# Sheet1.net
KiCad netlist of a schematic drawn in Altium Designer
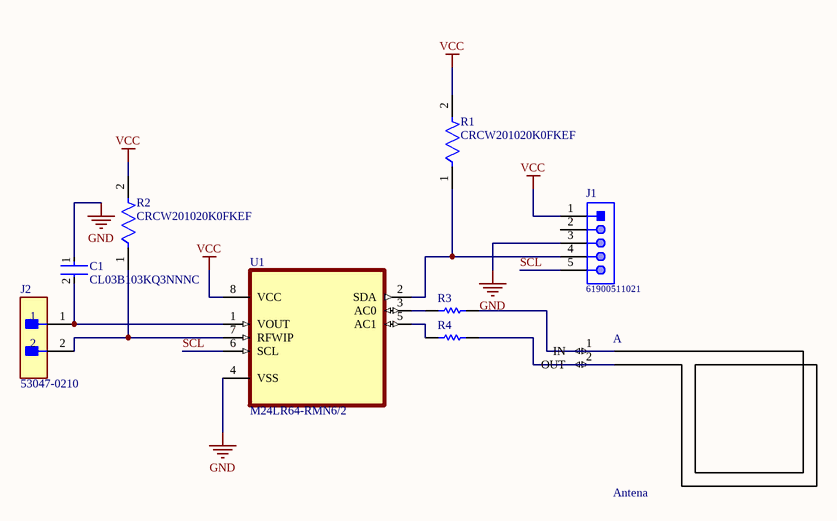
[diagram p0: Sheet1.SchDoc]

(export (version "E")
  (design (tool "Eeschema 10.0.6"))
  (components
    (comp (ref "A") (value "Antena") (footprint "Antena2") (libsource (lib "ANtene_symbol") (part "Antena")))
    (comp (ref "C1")
      (value "CL03B103KQ3NNNC")
      (footprint "FP-CL03-IPC_C")
      (description "Cap Ceramic 10nF 6.3V X7R ±10% Pad SMD 0201 +125°C T/R")
      (fields (field (name "TOLERANCE") "10%"))
      (libsource (lib "Altium Content Vault") (part "b4654b650e69147ec39a6b967a45e02"))
    )
    (comp (ref "J1")
      (value "61900511021")
      (footprint "61900511021")
      (description "Male Bottom Locking Header WR-WTB, THT, Right Angled, pitch 2.54 mm, 1 x 5 position")
      (fields (field (name "MANUFACTURER") "Wurth Elektronik") (field (name "PUBLISHER") "WurthElektronik"))
      (libsource (lib "Altium Content Vault") (part "WE-CN-1P-M-R5"))
    )
    (comp (ref "J2")
      (value "53047-0210")
      (footprint "FP-53047-0210-MFG")
      (description "CONN HEADER VERT 2POS 1.25MM")
      (fields
        (field (name "OCTOPART") "https://octopart.com/53047-0210-molex-276772")
        (field (name "MANUFACTURER") "Molex")
      )
      (libsource (lib "Altium Content Vault") (part "3bc925449376181038e59eaffc5286c"))
    )
    (comp (ref "R1")
      (value "CRCW201020K0FKEF")
      (footprint "FP-CRCW2010-e3-MFG")
      (description "RES Thick Film, 20kΩ, 1%, 0.75W, 100ppm/°C, 2010")
      (fields (field (name "TOLERANCE") "1%"))
      (libsource (lib "Altium Content Vault") (part "1029c3af85768c4190bb7ad29bc67b5"))
    )
    (comp (ref "R2")
      (value "CRCW201020K0FKEF")
      (footprint "FP-CRCW2010-e3-MFG")
      (description "RES Thick Film, 20kΩ, 1%, 0.75W, 100ppm/°C, 2010")
      (fields (field (name "TOLERANCE") "1%"))
      (libsource (lib "Altium Content Vault") (part "1029c3af85768c4190bb7ad29bc67b5"))
    )
    (comp (ref "R3")
      (value "RC1206FR-071RL")
      (footprint "RESC3116X65X40LL10T20")
      (description "Chip Resistor, 1 Ohm, +/- 1%, 250 mW, -55 to 155 degC, 1206 (3216 Metric), RoHS, Tape and Reel")
      (fields (field (name "MANUFACTURER") "Yageo") (field (name "TOLERANCE") "1%"))
      (libsource (lib "Altium Content Vault") (part "RES-2"))
    )
    (comp (ref "R4")
      (value "RC1206FR-071RL")
      (footprint "RESC3116X65X40LL10T20")
      (description "Chip Resistor, 1 Ohm, +/- 1%, 250 mW, -55 to 155 degC, 1206 (3216 Metric), RoHS, Tape and Reel")
      (fields (field (name "MANUFACTURER") "Yageo") (field (name "TOLERANCE") "1%"))
      (libsource (lib "Altium Content Vault") (part "RES-2"))
    )
    (comp (ref "U1")
      (value "M24LR64-RMN6/2")
      (footprint "SOIC127P600X175-8N")
      (description "64 Kbit EEPROM")
      (fields (field (name "MP") "M24LR64-RMN6-2"))
      (libsource (lib "M24LR64-RMN6_2") (part "M24LR64-RMN6/2"))
    )
  )
  (nets
    (net (code "1") (name "/SCL") (class "Default")
      (node (ref "J1") (pin "5") (pinfunction "5_5") (pintype "passive"))
      (node (ref "U1") (pin "6") (pinfunction "SCL_6") (pintype "input"))
    )
    (net (code "2") (name "GND") (class "Default")
      (node (ref "C1") (pin "1") (pinfunction "1_1") (pintype "passive"))
      (node (ref "J1") (pin "3") (pinfunction "3_3") (pintype "passive"))
      (node (ref "U1") (pin "4") (pinfunction "VSS_4") (pintype "power_in"))
    )
    (net (code "3") (name "Net-(A-IN)") (class "Default")
      (node (ref "A") (pin "1") (pinfunction "IN_1") (pintype "bidirectional"))
      (node (ref "R3") (pin "2") (pinfunction "2_2") (pintype "passive"))
    )
    (net (code "4") (name "Net-(A-OUT)") (class "Default")
      (node (ref "A") (pin "2") (pinfunction "OUT_2") (pintype "bidirectional"))
      (node (ref "R4") (pin "2") (pinfunction "2_2") (pintype "passive"))
    )
    (net (code "5") (name "Net-(U1-AC0)") (class "Default")
      (node (ref "R3") (pin "1") (pinfunction "1_1") (pintype "passive"))
      (node (ref "U1") (pin "3") (pinfunction "AC0_3") (pintype "bidirectional"))
    )
    (net (code "6") (name "Net-(U1-AC1)") (class "Default")
      (node (ref "R4") (pin "1") (pinfunction "1_1") (pintype "passive"))
      (node (ref "U1") (pin "5") (pinfunction "AC1_5") (pintype "bidirectional"))
    )
    (net (code "7") (name "Net-(U1-RFWIP)") (class "Default")
      (node (ref "J2") (pin "2") (pinfunction "2_2") (pintype "passive"))
      (node (ref "R2") (pin "1") (pinfunction "1_1") (pintype "passive"))
      (node (ref "U1") (pin "7") (pinfunction "RFWIP_7") (pintype "input"))
    )
    (net (code "8") (name "Net-(U1-SDA)") (class "Default")
      (node (ref "J1") (pin "4") (pinfunction "4_4") (pintype "passive"))
      (node (ref "R1") (pin "1") (pinfunction "1_1") (pintype "passive"))
      (node (ref "U1") (pin "2") (pinfunction "SDA_2") (pintype "output"))
    )
    (net (code "9") (name "Net-(U1-VOUT)") (class "Default")
      (node (ref "C1") (pin "2") (pinfunction "2_2") (pintype "passive"))
      (node (ref "J2") (pin "1") (pinfunction "1_1") (pintype "passive"))
      (node (ref "U1") (pin "1") (pinfunction "VOUT_1") (pintype "input"))
    )
    (net (code "10") (name "VCC") (class "Default")
      (node (ref "J1") (pin "1") (pinfunction "1_1") (pintype "passive"))
      (node (ref "R1") (pin "2") (pinfunction "2_2") (pintype "passive"))
      (node (ref "R2") (pin "2") (pinfunction "2_2") (pintype "passive"))
      (node (ref "U1") (pin "8") (pinfunction "VCC_8") (pintype "power_in"))
    )
    (net (code "11") (name "unconnected-(J1-Pad2)") (class "Default")
      (node (ref "J1") (pin "2") (pinfunction "2_2") (pintype "passive"))
    )
  )
)
